# MTX_pic_piggyback_V11.net
KiCad netlist of a schematic drawn in EAGLE
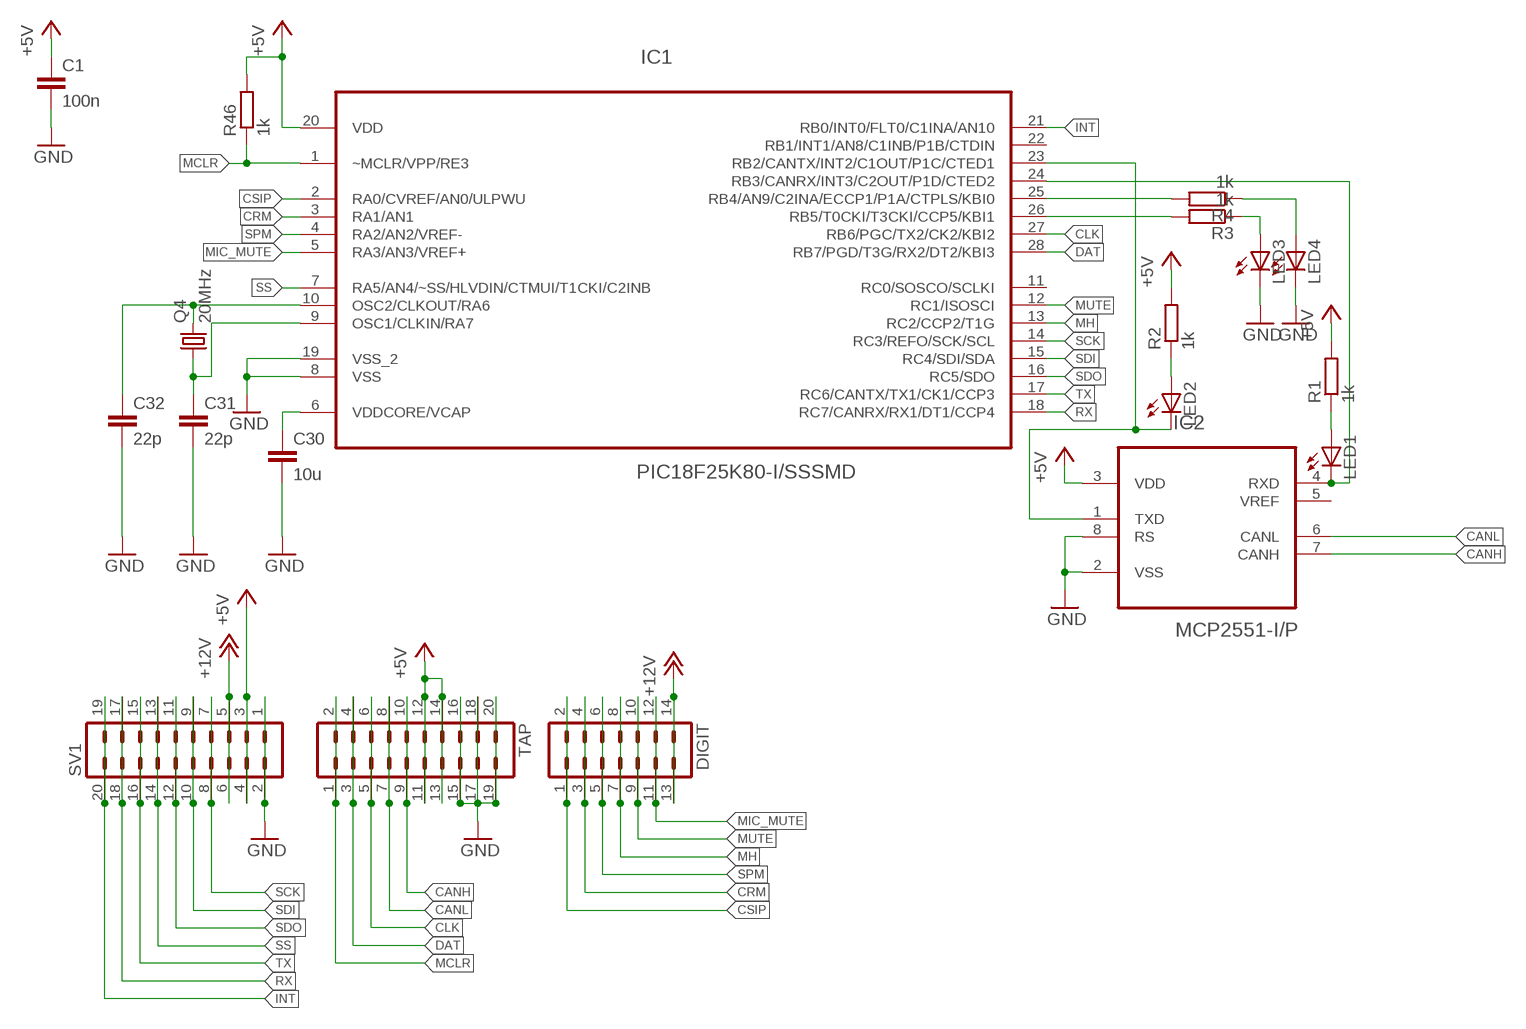
[diagram p0: schematic, sheet 1]

(export (version "E")
  (design (tool "Eeschema 10.0.6"))
  (components
    (comp (ref "C1")
      (value "100n")
      (footprint "eagle-import:C0805")
      (libsource (lib "eagle-import") (part "C-EUC0805"))
    )
    (comp (ref "C30")
      (value "10u")
      (footprint "eagle-import:C0805")
      (libsource (lib "eagle-import") (part "C-EUC0805"))
    )
    (comp (ref "C31")
      (value "22p")
      (footprint "eagle-import:C0805")
      (libsource (lib "eagle-import") (part "C-EUC0805"))
    )
    (comp (ref "C32")
      (value "22p")
      (footprint "eagle-import:C0805")
      (libsource (lib "eagle-import") (part "C-EUC0805"))
    )
    (comp (ref "DIGIT")
      (value "MA07-2")
      (footprint "eagle-import:MA07-2")
      (libsource (lib "eagle-import") (part "MA07-2"))
    )
    (comp (ref "IC1")
      (value "PIC18F25K80-I/SSSMD")
      (footprint "eagle-import:SOP65P780X200-28N")
      (libsource (lib "eagle-import") (part "PIC18F25K80-I/SSSMD"))
    )
    (comp (ref "IC2")
      (value "MCP2551-I/P")
      (footprint "eagle-import:DIP254P762X432-8")
      (libsource (lib "eagle-import") (part "MCP2551-I/P"))
    )
    (comp (ref "LED1")
      (value "LEDCHIP-LED0805")
      (footprint "eagle-import:CHIP-LED0805")
      (libsource (lib "eagle-import") (part "LEDCHIP-LED0805"))
    )
    (comp (ref "LED2")
      (value "LEDCHIP-LED0805")
      (footprint "eagle-import:CHIP-LED0805")
      (libsource (lib "eagle-import") (part "LEDCHIP-LED0805"))
    )
    (comp (ref "LED3")
      (value "LEDCHIP-LED0805")
      (footprint "eagle-import:CHIP-LED0805")
      (libsource (lib "eagle-import") (part "LEDCHIP-LED0805"))
    )
    (comp (ref "LED4")
      (value "LEDCHIP-LED0805")
      (footprint "eagle-import:CHIP-LED0805")
      (libsource (lib "eagle-import") (part "LEDCHIP-LED0805"))
    )
    (comp (ref "Q4")
      (value "20MHz")
      (footprint "eagle-import:HC49UP")
      (libsource (lib "eagle-import") (part "CRYSTALHC49UP"))
    )
    (comp (ref "R1")
      (value "1k")
      (footprint "eagle-import:R0805")
      (libsource (lib "eagle-import") (part "R-EU_R0805"))
    )
    (comp (ref "R2")
      (value "1k")
      (footprint "eagle-import:R0805")
      (libsource (lib "eagle-import") (part "R-EU_R0805"))
    )
    (comp (ref "R3")
      (value "1k")
      (footprint "eagle-import:R0805")
      (libsource (lib "eagle-import") (part "R-EU_R0805"))
    )
    (comp (ref "R4")
      (value "1k")
      (footprint "eagle-import:R0805")
      (libsource (lib "eagle-import") (part "R-EU_R0805"))
    )
    (comp (ref "R46")
      (value "1k")
      (footprint "eagle-import:R0805")
      (libsource (lib "eagle-import") (part "R-EU_R0805"))
    )
    (comp (ref "SV1")
      (value "MA10-2")
      (footprint "eagle-import:MA10-2")
      (libsource (lib "eagle-import") (part "MA10-2"))
    )
    (comp (ref "TAP")
      (value "MA10-2")
      (footprint "eagle-import:MA10-2")
      (libsource (lib "eagle-import") (part "MA10-2"))
    )
  )
  (nets
    (net (code "1") (name "+5V") (class "Default")
      (node (ref "C1") (pin "1") (pinfunction "1_1") (pintype "passive"))
      (node (ref "IC1") (pin "20") (pinfunction "VDD_20") (pintype "power_in"))
      (node (ref "IC2") (pin "3") (pinfunction "VDD_3") (pintype "power_in"))
      (node (ref "R1") (pin "2") (pinfunction "2_2") (pintype "passive"))
      (node (ref "R2") (pin "2") (pinfunction "2_2") (pintype "passive"))
      (node (ref "R46") (pin "2") (pinfunction "2_2") (pintype "passive"))
      (node (ref "SV1") (pin "3") (pinfunction "3_3") (pintype "passive"))
      (node (ref "SV1") (pin "4") (pinfunction "4_4") (pintype "passive"))
      (node (ref "TAP") (pin "11") (pinfunction "11_11") (pintype "passive"))
      (node (ref "TAP") (pin "12") (pinfunction "12_12") (pintype "passive"))
      (node (ref "TAP") (pin "13") (pinfunction "13_13") (pintype "passive"))
      (node (ref "TAP") (pin "14") (pinfunction "14_14") (pintype "passive"))
    )
    (net (code "2") (name "+12V") (class "Default")
      (node (ref "DIGIT") (pin "13") (pinfunction "13_13") (pintype "passive"))
      (node (ref "DIGIT") (pin "14") (pinfunction "14_14") (pintype "passive"))
      (node (ref "SV1") (pin "5") (pinfunction "5_5") (pintype "passive"))
      (node (ref "SV1") (pin "6") (pinfunction "6_6") (pintype "passive"))
    )
    (net (code "3") (name "CANH") (class "Default")
      (node (ref "IC2") (pin "7") (pinfunction "CANH_7") (pintype "bidirectional"))
      (node (ref "TAP") (pin "10") (pinfunction "10_10") (pintype "passive"))
      (node (ref "TAP") (pin "9") (pinfunction "9_9") (pintype "passive"))
    )
    (net (code "4") (name "CANL") (class "Default")
      (node (ref "IC2") (pin "6") (pinfunction "CANL_6") (pintype "bidirectional"))
      (node (ref "TAP") (pin "7") (pinfunction "7_7") (pintype "passive"))
      (node (ref "TAP") (pin "8") (pinfunction "8_8") (pintype "passive"))
    )
    (net (code "5") (name "CLK") (class "Default")
      (node (ref "IC1") (pin "27") (pinfunction "RB6/PGC/TX2/CK2/KBI2_27") (pintype "bidirectional"))
      (node (ref "TAP") (pin "5") (pinfunction "5_5") (pintype "passive"))
      (node (ref "TAP") (pin "6") (pinfunction "6_6") (pintype "passive"))
    )
    (net (code "6") (name "CRM") (class "Default")
      (node (ref "DIGIT") (pin "3") (pinfunction "3_3") (pintype "passive"))
      (node (ref "DIGIT") (pin "4") (pinfunction "4_4") (pintype "passive"))
      (node (ref "IC1") (pin "3") (pinfunction "RA1/AN1_3") (pintype "bidirectional"))
    )
    (net (code "7") (name "CSIP") (class "Default")
      (node (ref "DIGIT") (pin "1") (pinfunction "1_1") (pintype "passive"))
      (node (ref "DIGIT") (pin "2") (pinfunction "2_2") (pintype "passive"))
      (node (ref "IC1") (pin "2") (pinfunction "RA0/CVREF/AN0/ULPWU_2") (pintype "bidirectional"))
    )
    (net (code "8") (name "DAT") (class "Default")
      (node (ref "IC1") (pin "28") (pinfunction "RB7/PGD/T3G/RX2/DT2/KBI3_28") (pintype "bidirectional"))
      (node (ref "TAP") (pin "3") (pinfunction "3_3") (pintype "passive"))
      (node (ref "TAP") (pin "4") (pinfunction "4_4") (pintype "passive"))
    )
    (net (code "9") (name "GND") (class "Default")
      (node (ref "C1") (pin "2") (pinfunction "2_2") (pintype "passive"))
      (node (ref "C30") (pin "2") (pinfunction "2_2") (pintype "passive"))
      (node (ref "C31") (pin "2") (pinfunction "2_2") (pintype "passive"))
      (node (ref "C32") (pin "2") (pinfunction "2_2") (pintype "passive"))
      (node (ref "IC1") (pin "19") (pinfunction "VSS_2_19") (pintype "power_in"))
      (node (ref "IC1") (pin "8") (pinfunction "VSS_8") (pintype "power_in"))
      (node (ref "IC2") (pin "2") (pinfunction "VSS_2") (pintype "power_in"))
      (node (ref "IC2") (pin "8") (pinfunction "RS_8") (pintype "input"))
      (node (ref "LED3") (pin "C") (pinfunction "C_C") (pintype "passive"))
      (node (ref "LED4") (pin "C") (pinfunction "C_C") (pintype "passive"))
      (node (ref "SV1") (pin "1") (pinfunction "1_1") (pintype "passive"))
      (node (ref "SV1") (pin "2") (pinfunction "2_2") (pintype "passive"))
      (node (ref "TAP") (pin "15") (pinfunction "15_15") (pintype "passive"))
      (node (ref "TAP") (pin "16") (pinfunction "16_16") (pintype "passive"))
      (node (ref "TAP") (pin "17") (pinfunction "17_17") (pintype "passive"))
      (node (ref "TAP") (pin "18") (pinfunction "18_18") (pintype "passive"))
      (node (ref "TAP") (pin "19") (pinfunction "19_19") (pintype "passive"))
      (node (ref "TAP") (pin "20") (pinfunction "20_20") (pintype "passive"))
    )
    (net (code "10") (name "INT") (class "Default")
      (node (ref "IC1") (pin "21") (pinfunction "RB0/INT0/FLT0/C1INA/AN10_21") (pintype "bidirectional"))
      (node (ref "SV1") (pin "19") (pinfunction "19_19") (pintype "passive"))
      (node (ref "SV1") (pin "20") (pinfunction "20_20") (pintype "passive"))
    )
    (net (code "11") (name "MCLR") (class "Default")
      (node (ref "IC1") (pin "1") (pinfunction "~{MCLR/VPP/RE3}_1") (pintype "input"))
      (node (ref "R46") (pin "1") (pinfunction "1_1") (pintype "passive"))
      (node (ref "TAP") (pin "1") (pinfunction "1_1") (pintype "passive"))
      (node (ref "TAP") (pin "2") (pinfunction "2_2") (pintype "passive"))
    )
    (net (code "12") (name "MH") (class "Default")
      (node (ref "DIGIT") (pin "7") (pinfunction "7_7") (pintype "passive"))
      (node (ref "DIGIT") (pin "8") (pinfunction "8_8") (pintype "passive"))
      (node (ref "IC1") (pin "13") (pinfunction "RC2/CCP2/T1G_13") (pintype "bidirectional"))
    )
    (net (code "13") (name "MIC_MUTE") (class "Default")
      (node (ref "DIGIT") (pin "11") (pinfunction "11_11") (pintype "passive"))
      (node (ref "DIGIT") (pin "12") (pinfunction "12_12") (pintype "passive"))
      (node (ref "IC1") (pin "5") (pinfunction "RA3/AN3/VREF+_5") (pintype "bidirectional"))
    )
    (net (code "14") (name "MUTE") (class "Default")
      (node (ref "DIGIT") (pin "10") (pinfunction "10_10") (pintype "passive"))
      (node (ref "DIGIT") (pin "9") (pinfunction "9_9") (pintype "passive"))
      (node (ref "IC1") (pin "12") (pinfunction "RC1/ISOSCI_12") (pintype "bidirectional"))
    )
    (net (code "15") (name "Net-(IC1-OSC1{slash}CLKIN{slash}RA7)") (class "Default")
      (node (ref "C31") (pin "1") (pinfunction "1_1") (pintype "passive"))
      (node (ref "IC1") (pin "9") (pinfunction "OSC1/CLKIN/RA7_9") (pintype "bidirectional"))
      (node (ref "Q4") (pin "1") (pinfunction "1_1") (pintype "passive"))
    )
    (net (code "16") (name "Net-(IC1-OSC2{slash}CLKOUT{slash}RA6)") (class "Default")
      (node (ref "C32") (pin "1") (pinfunction "1_1") (pintype "passive"))
      (node (ref "IC1") (pin "10") (pinfunction "OSC2/CLKOUT/RA6_10") (pintype "bidirectional"))
      (node (ref "Q4") (pin "2") (pinfunction "2_2") (pintype "passive"))
    )
    (net (code "17") (name "Net-(IC1-RB2{slash}CANTX{slash}INT2{slash}C1OUT{slash}P1C{slash}CTED1)") (class "Default")
      (node (ref "IC1") (pin "23") (pinfunction "RB2/CANTX/INT2/C1OUT/P1C/CTED1_23") (pintype "bidirectional"))
      (node (ref "IC2") (pin "1") (pinfunction "TXD_1") (pintype "input"))
      (node (ref "LED2") (pin "C") (pinfunction "C_C") (pintype "passive"))
    )
    (net (code "18") (name "Net-(IC1-RB3{slash}CANRX{slash}INT3{slash}C2OUT{slash}P1D{slash}CTED2)") (class "Default")
      (node (ref "IC1") (pin "24") (pinfunction "RB3/CANRX/INT3/C2OUT/P1D/CTED2_24") (pintype "bidirectional"))
      (node (ref "IC2") (pin "4") (pinfunction "RXD_4") (pintype "output"))
      (node (ref "LED1") (pin "C") (pinfunction "C_C") (pintype "passive"))
    )
    (net (code "19") (name "Net-(IC1-RB4{slash}AN9{slash}C2INA{slash}ECCP1{slash}P1A{slash}CTPLS{slash}KBI0)") (class "Default")
      (node (ref "IC1") (pin "25") (pinfunction "RB4/AN9/C2INA/ECCP1/P1A/CTPLS/KBI0_25") (pintype "bidirectional"))
      (node (ref "R4") (pin "2") (pinfunction "2_2") (pintype "passive"))
    )
    (net (code "20") (name "Net-(IC1-RB5{slash}T0CKI{slash}T3CKI{slash}CCP5{slash}KBI1)") (class "Default")
      (node (ref "IC1") (pin "26") (pinfunction "RB5/T0CKI/T3CKI/CCP5/KBI1_26") (pintype "bidirectional"))
      (node (ref "R3") (pin "2") (pinfunction "2_2") (pintype "passive"))
    )
    (net (code "21") (name "Net-(IC1-VDDCORE{slash}VCAP)") (class "Default")
      (node (ref "C30") (pin "1") (pinfunction "1_1") (pintype "passive"))
      (node (ref "IC1") (pin "6") (pinfunction "VDDCORE/VCAP_6") (pintype "bidirectional"))
    )
    (net (code "22") (name "Net-(LED1-PadA)") (class "Default")
      (node (ref "LED1") (pin "A") (pinfunction "A_A") (pintype "passive"))
      (node (ref "R1") (pin "1") (pinfunction "1_1") (pintype "passive"))
    )
    (net (code "23") (name "Net-(LED2-PadA)") (class "Default")
      (node (ref "LED2") (pin "A") (pinfunction "A_A") (pintype "passive"))
      (node (ref "R2") (pin "1") (pinfunction "1_1") (pintype "passive"))
    )
    (net (code "24") (name "Net-(LED3-PadA)") (class "Default")
      (node (ref "LED3") (pin "A") (pinfunction "A_A") (pintype "passive"))
      (node (ref "R3") (pin "1") (pinfunction "1_1") (pintype "passive"))
    )
    (net (code "25") (name "Net-(LED4-PadA)") (class "Default")
      (node (ref "LED4") (pin "A") (pinfunction "A_A") (pintype "passive"))
      (node (ref "R4") (pin "1") (pinfunction "1_1") (pintype "passive"))
    )
    (net (code "26") (name "RX") (class "Default")
      (node (ref "IC1") (pin "18") (pinfunction "RC7/CANRX/RX1/DT1/CCP4_18") (pintype "bidirectional"))
      (node (ref "SV1") (pin "17") (pinfunction "17_17") (pintype "passive"))
      (node (ref "SV1") (pin "18") (pinfunction "18_18") (pintype "passive"))
    )
    (net (code "27") (name "SCK") (class "Default")
      (node (ref "IC1") (pin "14") (pinfunction "RC3/REFO/SCK/SCL_14") (pintype "bidirectional"))
      (node (ref "SV1") (pin "7") (pinfunction "7_7") (pintype "passive"))
      (node (ref "SV1") (pin "8") (pinfunction "8_8") (pintype "passive"))
    )
    (net (code "28") (name "SDI") (class "Default")
      (node (ref "IC1") (pin "15") (pinfunction "RC4/SDI/SDA_15") (pintype "bidirectional"))
      (node (ref "SV1") (pin "10") (pinfunction "10_10") (pintype "passive"))
      (node (ref "SV1") (pin "9") (pinfunction "9_9") (pintype "passive"))
    )
    (net (code "29") (name "SDO") (class "Default")
      (node (ref "IC1") (pin "16") (pinfunction "RC5/SDO_16") (pintype "bidirectional"))
      (node (ref "SV1") (pin "11") (pinfunction "11_11") (pintype "passive"))
      (node (ref "SV1") (pin "12") (pinfunction "12_12") (pintype "passive"))
    )
    (net (code "30") (name "SPM") (class "Default")
      (node (ref "DIGIT") (pin "5") (pinfunction "5_5") (pintype "passive"))
      (node (ref "DIGIT") (pin "6") (pinfunction "6_6") (pintype "passive"))
      (node (ref "IC1") (pin "4") (pinfunction "RA2/AN2/VREF-_4") (pintype "bidirectional"))
    )
    (net (code "31") (name "SS") (class "Default")
      (node (ref "IC1") (pin "7") (pinfunction "RA5/AN4/~{SS/HLVDIN/CTMUI/T1CKI/C2INB}_7") (pintype "bidirectional"))
      (node (ref "SV1") (pin "13") (pinfunction "13_13") (pintype "passive"))
      (node (ref "SV1") (pin "14") (pinfunction "14_14") (pintype "passive"))
    )
    (net (code "32") (name "TX") (class "Default")
      (node (ref "IC1") (pin "17") (pinfunction "RC6/CANTX/TX1/CK1/CCP3_17") (pintype "bidirectional"))
      (node (ref "SV1") (pin "15") (pinfunction "15_15") (pintype "passive"))
      (node (ref "SV1") (pin "16") (pinfunction "16_16") (pintype "passive"))
    )
    (net (code "33") (name "unconnected-(IC1-RB1{slash}INT1{slash}AN8{slash}C1INB{slash}P1B{slash}CTDIN-Pad22)") (class "Default")
      (node (ref "IC1") (pin "22") (pinfunction "RB1/INT1/AN8/C1INB/P1B/CTDIN_22") (pintype "bidirectional"))
    )
    (net (code "34") (name "unconnected-(IC1-RC0{slash}SOSCO{slash}SCLKI-Pad11)") (class "Default")
      (node (ref "IC1") (pin "11") (pinfunction "RC0/SOSCO/SCLKI_11") (pintype "bidirectional"))
    )
    (net (code "35") (name "unconnected-(IC2-VREF-Pad5)") (class "Default")
      (node (ref "IC2") (pin "5") (pinfunction "VREF_5") (pintype "output"))
    )
  )
)
